# Rev4.net
KiCad netlist of a schematic drawn in EAGLE
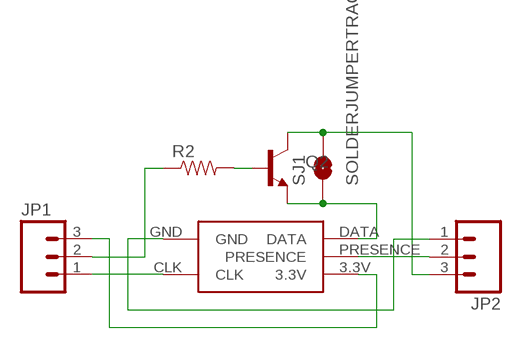
[diagram p0: schematic, sheet 1]

(export (version "E")
  (design (tool "Eeschema 10.0.6"))
  (components
    (comp (ref "JP1")
      (value "M03PTH")
      (footprint "eagle-import:1X03")
      (libsource (lib "eagle-import") (part "M03PTH"))
    )
    (comp (ref "JP2")
      (value "M03PTH")
      (footprint "eagle-import:1X03")
      (libsource (lib "eagle-import") (part "M03PTH"))
    )
    (comp (ref "Q2")
      (value "TRANSISTOR_NPNSOT23")
      (footprint "eagle-import:SOT23")
      (libsource (lib "eagle-import") (part "TRANSISTOR_NPNSOT23"))
    )
    (comp (ref "R2")
      (value "RESISTOR0603")
      (footprint "eagle-import:0603-RES")
      (libsource (lib "eagle-import") (part "RESISTOR0603"))
    )
    (comp (ref "SJ1")
      (value "SOLDERJUMPERTRACE")
      (footprint "eagle-import:SJ_2S-TRACE")
      (libsource (lib "eagle-import") (part "SOLDERJUMPERTRACE"))
    )
    (comp (ref "U$1")
      (value "NUNCHUCKLOCL")
      (footprint "eagle-import:NUNCHUCK-LOCK")
      (libsource (lib "eagle-import") (part "NUNCHUCKLOCL"))
    )
  )
  (nets
    (net (code "1") (name "Net-(JP1-Pad1)") (class "Default")
      (node (ref "JP1") (pin "1") (pinfunction "1_1") (pintype "passive"))
      (node (ref "U$1") (pin "CLK") (pinfunction "CLK_CLK") (pintype "bidirectional"))
    )
    (net (code "2") (name "Net-(JP1-Pad2)") (class "Default")
      (node (ref "JP1") (pin "2") (pinfunction "2_2") (pintype "passive"))
      (node (ref "R2") (pin "1") (pinfunction "1_1") (pintype "passive"))
    )
    (net (code "3") (name "Net-(JP1-Pad3)") (class "Default")
      (node (ref "JP1") (pin "3") (pinfunction "3_3") (pintype "passive"))
      (node (ref "U$1") (pin "3.3V") (pinfunction "3.3V_3.3V") (pintype "bidirectional"))
    )
    (net (code "4") (name "Net-(JP2-Pad1)") (class "Default")
      (node (ref "JP2") (pin "1") (pinfunction "1_1") (pintype "passive"))
      (node (ref "U$1") (pin "GND") (pinfunction "GND_GND") (pintype "bidirectional"))
    )
    (net (code "5") (name "Net-(JP2-Pad2)") (class "Default")
      (node (ref "JP2") (pin "2") (pinfunction "2_2") (pintype "passive"))
      (node (ref "U$1") (pin "PRESENCE") (pinfunction "PRESENCE_PRESENCE") (pintype "bidirectional"))
    )
    (net (code "6") (name "Net-(Q2-B)") (class "Default")
      (node (ref "Q2") (pin "1") (pinfunction "B_1") (pintype "passive"))
      (node (ref "R2") (pin "2") (pinfunction "2_2") (pintype "passive"))
    )
    (net (code "7") (name "Net-(Q2-C)") (class "Default")
      (node (ref "JP2") (pin "3") (pinfunction "3_3") (pintype "passive"))
      (node (ref "Q2") (pin "3") (pinfunction "C_3") (pintype "passive"))
      (node (ref "SJ1") (pin "2") (pinfunction "2_2") (pintype "passive"))
    )
    (net (code "8") (name "Net-(Q2-E)") (class "Default")
      (node (ref "Q2") (pin "2") (pinfunction "E_2") (pintype "passive"))
      (node (ref "SJ1") (pin "1") (pinfunction "1_1") (pintype "passive"))
      (node (ref "U$1") (pin "DATA") (pinfunction "DATA_DATA") (pintype "bidirectional"))
    )
  )
)
